# 4KB_SRAM_SCH_EASYEDA.net
KiCad netlist of a schematic drawn in EasyEDA
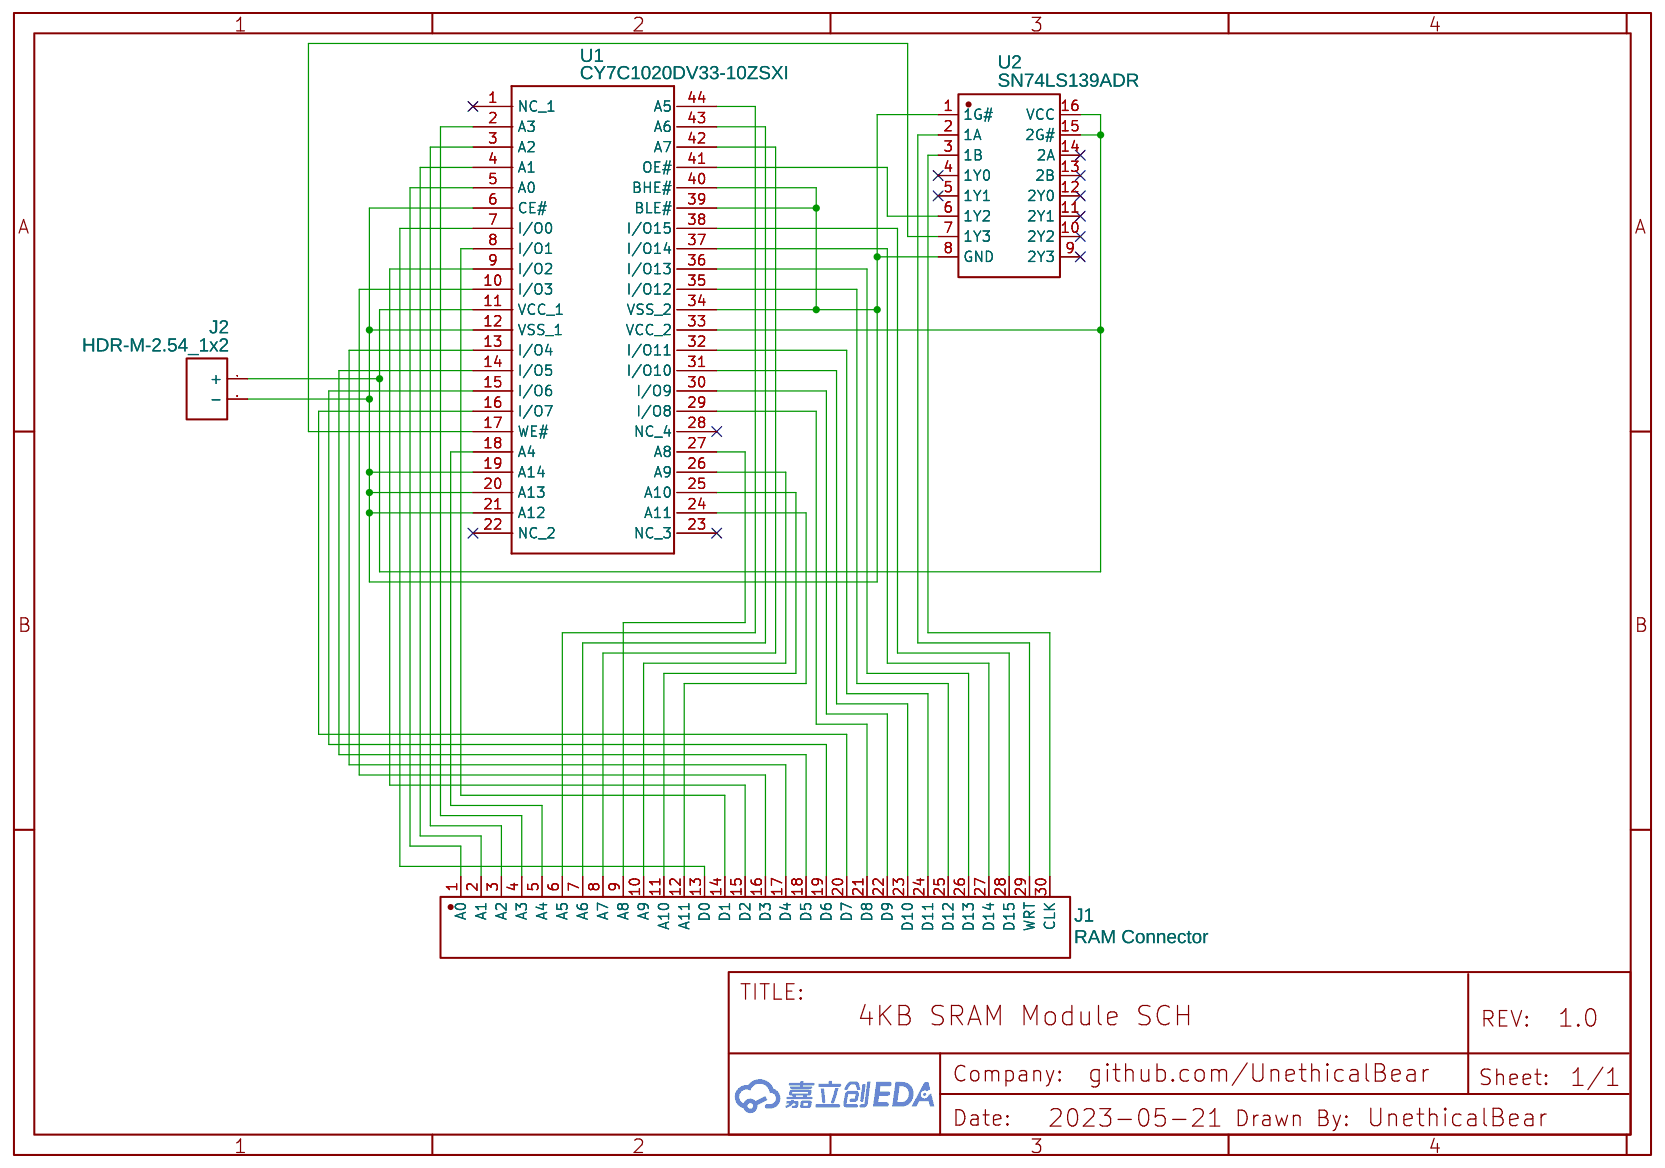
[diagram p0: schematic sheet]

(export (version "E")
  (design (tool "Eeschema 10.0.6"))
  (components
    (comp (ref "J1") (value "RAM Connector") (libsource (lib "") (part "R.C.")))
    (comp (ref "J2")
      (value "HDR-M-2.54_1x2")
      (fields (field (name "BOM_Supplier Part") "C124375"))
      (libsource (lib "") (part "HDR-M-2.54_1x2"))
    )
    (comp (ref "U1") (value "CY7C1020DV33-10ZSXI") (libsource (lib "") (part "CY7C1020DV33-10ZSXI")))
    (comp (ref "U2")
      (value "SN74LS139ADR")
      (fields (field (name "BOM_Supplier Part") "C7738"))
      (libsource (lib "") (part "SN74LS139ADR"))
    )
  )
  (nets
    (net (code "1") (name "Net-(J1-A0)") (class "Default")
      (node (ref "J1") (pin "1") (pinfunction "A0_1") (pintype "unspecified"))
      (node (ref "U1") (pin "5") (pinfunction "A0_5") (pintype "bidirectional"))
    )
    (net (code "2") (name "Net-(J1-A1)") (class "Default")
      (node (ref "J1") (pin "2") (pinfunction "A1_2") (pintype "unspecified"))
      (node (ref "U1") (pin "4") (pinfunction "A1_4") (pintype "bidirectional"))
    )
    (net (code "3") (name "Net-(J1-A2)") (class "Default")
      (node (ref "J1") (pin "3") (pinfunction "A2_3") (pintype "unspecified"))
      (node (ref "U1") (pin "3") (pinfunction "A2_3") (pintype "bidirectional"))
    )
    (net (code "4") (name "Net-(J1-A3)") (class "Default")
      (node (ref "J1") (pin "4") (pinfunction "A3_4") (pintype "unspecified"))
      (node (ref "U1") (pin "2") (pinfunction "A3_2") (pintype "bidirectional"))
    )
    (net (code "5") (name "Net-(J1-A4)") (class "Default")
      (node (ref "J1") (pin "5") (pinfunction "A4_5") (pintype "unspecified"))
      (node (ref "U1") (pin "18") (pinfunction "A4_18") (pintype "bidirectional"))
    )
    (net (code "6") (name "Net-(J1-A5)") (class "Default")
      (node (ref "J1") (pin "6") (pinfunction "A5_6") (pintype "unspecified"))
      (node (ref "U1") (pin "44") (pinfunction "A5_44") (pintype "bidirectional"))
    )
    (net (code "7") (name "Net-(J1-A6)") (class "Default")
      (node (ref "J1") (pin "7") (pinfunction "A6_7") (pintype "unspecified"))
      (node (ref "U1") (pin "43") (pinfunction "A6_43") (pintype "bidirectional"))
    )
    (net (code "8") (name "Net-(J1-A7)") (class "Default")
      (node (ref "J1") (pin "8") (pinfunction "A7_8") (pintype "unspecified"))
      (node (ref "U1") (pin "42") (pinfunction "A7_42") (pintype "bidirectional"))
    )
    (net (code "9") (name "Net-(J1-A8)") (class "Default")
      (node (ref "J1") (pin "9") (pinfunction "A8_9") (pintype "unspecified"))
      (node (ref "U1") (pin "27") (pinfunction "A8_27") (pintype "bidirectional"))
    )
    (net (code "10") (name "Net-(J1-A9)") (class "Default")
      (node (ref "J1") (pin "10") (pinfunction "A9_10") (pintype "unspecified"))
      (node (ref "U1") (pin "26") (pinfunction "A9_26") (pintype "bidirectional"))
    )
    (net (code "11") (name "Net-(J1-A10)") (class "Default")
      (node (ref "J1") (pin "11") (pinfunction "A10_11") (pintype "unspecified"))
      (node (ref "U1") (pin "25") (pinfunction "A10_25") (pintype "bidirectional"))
    )
    (net (code "12") (name "Net-(J1-A11)") (class "Default")
      (node (ref "J1") (pin "12") (pinfunction "A11_12") (pintype "unspecified"))
      (node (ref "U1") (pin "24") (pinfunction "A11_24") (pintype "bidirectional"))
    )
    (net (code "13") (name "Net-(J1-CLK)") (class "Default")
      (node (ref "J1") (pin "30") (pinfunction "CLK_30") (pintype "unspecified"))
      (node (ref "U2") (pin "3") (pinfunction "1B_3") (pintype "unspecified"))
    )
    (net (code "14") (name "Net-(J1-D0)") (class "Default")
      (node (ref "J1") (pin "13") (pinfunction "D0_13") (pintype "unspecified"))
      (node (ref "U1") (pin "7") (pinfunction "I/O0_7") (pintype "bidirectional"))
    )
    (net (code "15") (name "Net-(J1-D1)") (class "Default")
      (node (ref "J1") (pin "14") (pinfunction "D1_14") (pintype "unspecified"))
      (node (ref "U1") (pin "8") (pinfunction "I/O1_8") (pintype "bidirectional"))
    )
    (net (code "16") (name "Net-(J1-D2)") (class "Default")
      (node (ref "J1") (pin "15") (pinfunction "D2_15") (pintype "unspecified"))
      (node (ref "U1") (pin "9") (pinfunction "I/O2_9") (pintype "bidirectional"))
    )
    (net (code "17") (name "Net-(J1-D3)") (class "Default")
      (node (ref "J1") (pin "16") (pinfunction "D3_16") (pintype "unspecified"))
      (node (ref "U1") (pin "10") (pinfunction "I/O3_10") (pintype "bidirectional"))
    )
    (net (code "18") (name "Net-(J1-D4)") (class "Default")
      (node (ref "J1") (pin "17") (pinfunction "D4_17") (pintype "unspecified"))
      (node (ref "U1") (pin "13") (pinfunction "I/O4_13") (pintype "bidirectional"))
    )
    (net (code "19") (name "Net-(J1-D5)") (class "Default")
      (node (ref "J1") (pin "18") (pinfunction "D5_18") (pintype "unspecified"))
      (node (ref "U1") (pin "14") (pinfunction "I/O5_14") (pintype "bidirectional"))
    )
    (net (code "20") (name "Net-(J1-D6)") (class "Default")
      (node (ref "J1") (pin "19") (pinfunction "D6_19") (pintype "unspecified"))
      (node (ref "U1") (pin "15") (pinfunction "I/O6_15") (pintype "bidirectional"))
    )
    (net (code "21") (name "Net-(J1-D7)") (class "Default")
      (node (ref "J1") (pin "20") (pinfunction "D7_20") (pintype "unspecified"))
      (node (ref "U1") (pin "16") (pinfunction "I/O7_16") (pintype "bidirectional"))
    )
    (net (code "22") (name "Net-(J1-D8)") (class "Default")
      (node (ref "J1") (pin "21") (pinfunction "D8_21") (pintype "unspecified"))
      (node (ref "U1") (pin "29") (pinfunction "I/O8_29") (pintype "bidirectional"))
    )
    (net (code "23") (name "Net-(J1-D9)") (class "Default")
      (node (ref "J1") (pin "22") (pinfunction "D9_22") (pintype "unspecified"))
      (node (ref "U1") (pin "30") (pinfunction "I/O9_30") (pintype "bidirectional"))
    )
    (net (code "24") (name "Net-(J1-D10)") (class "Default")
      (node (ref "J1") (pin "23") (pinfunction "D10_23") (pintype "unspecified"))
      (node (ref "U1") (pin "31") (pinfunction "I/O10_31") (pintype "bidirectional"))
    )
    (net (code "25") (name "Net-(J1-D11)") (class "Default")
      (node (ref "J1") (pin "24") (pinfunction "D11_24") (pintype "unspecified"))
      (node (ref "U1") (pin "32") (pinfunction "I/O11_32") (pintype "bidirectional"))
    )
    (net (code "26") (name "Net-(J1-D12)") (class "Default")
      (node (ref "J1") (pin "25") (pinfunction "D12_25") (pintype "unspecified"))
      (node (ref "U1") (pin "35") (pinfunction "I/O12_35") (pintype "bidirectional"))
    )
    (net (code "27") (name "Net-(J1-D13)") (class "Default")
      (node (ref "J1") (pin "26") (pinfunction "D13_26") (pintype "unspecified"))
      (node (ref "U1") (pin "36") (pinfunction "I/O13_36") (pintype "bidirectional"))
    )
    (net (code "28") (name "Net-(J1-D14)") (class "Default")
      (node (ref "J1") (pin "27") (pinfunction "D14_27") (pintype "unspecified"))
      (node (ref "U1") (pin "37") (pinfunction "I/O14_37") (pintype "bidirectional"))
    )
    (net (code "29") (name "Net-(J1-D15)") (class "Default")
      (node (ref "J1") (pin "28") (pinfunction "D15_28") (pintype "unspecified"))
      (node (ref "U1") (pin "38") (pinfunction "I/O15_38") (pintype "bidirectional"))
    )
    (net (code "30") (name "Net-(J1-WRT)") (class "Default")
      (node (ref "J1") (pin "29") (pinfunction "WRT_29") (pintype "unspecified"))
      (node (ref "U2") (pin "2") (pinfunction "1A_2") (pintype "unspecified"))
    )
    (net (code "31") (name "Net-(J2-+)") (class "Default")
      (node (ref "J2") (pin "1") (pinfunction "+_1") (pintype "unspecified"))
      (node (ref "U1") (pin "11") (pinfunction "VCC_1_11") (pintype "bidirectional"))
      (node (ref "U1") (pin "33") (pinfunction "VCC_2_33") (pintype "bidirectional"))
      (node (ref "U2") (pin "15") (pinfunction "2G#_15") (pintype "unspecified"))
      (node (ref "U2") (pin "16") (pinfunction "VCC_16") (pintype "unspecified"))
    )
    (net (code "32") (name "Net-(J2--)") (class "Default")
      (node (ref "J2") (pin "2") (pinfunction "-_2") (pintype "unspecified"))
      (node (ref "U1") (pin "12") (pinfunction "VSS_1_12") (pintype "bidirectional"))
      (node (ref "U1") (pin "19") (pinfunction "A14_19") (pintype "bidirectional"))
      (node (ref "U1") (pin "20") (pinfunction "A13_20") (pintype "bidirectional"))
      (node (ref "U1") (pin "21") (pinfunction "A12_21") (pintype "bidirectional"))
      (node (ref "U1") (pin "34") (pinfunction "VSS_2_34") (pintype "bidirectional"))
      (node (ref "U1") (pin "39") (pinfunction "BLE#_39") (pintype "bidirectional"))
      (node (ref "U1") (pin "40") (pinfunction "BHE#_40") (pintype "bidirectional"))
      (node (ref "U1") (pin "6") (pinfunction "CE#_6") (pintype "bidirectional"))
      (node (ref "U2") (pin "1") (pinfunction "1G#_1") (pintype "unspecified"))
      (node (ref "U2") (pin "8") (pinfunction "GND_8") (pintype "unspecified"))
    )
    (net (code "33") (name "Net-(U1-OE#)") (class "Default")
      (node (ref "U1") (pin "41") (pinfunction "OE#_41") (pintype "bidirectional"))
      (node (ref "U2") (pin "6") (pinfunction "1Y2_6") (pintype "unspecified"))
    )
    (net (code "34") (name "Net-(U1-WE#)") (class "Default")
      (node (ref "U1") (pin "17") (pinfunction "WE#_17") (pintype "bidirectional"))
      (node (ref "U2") (pin "7") (pinfunction "1Y3_7") (pintype "unspecified"))
    )
    (net (code "35") (name "unconnected-(U1-NC_1-Pad1)") (class "Default")
      (node (ref "U1") (pin "1") (pinfunction "NC_1_1") (pintype "bidirectional+no_connect"))
    )
    (net (code "36") (name "unconnected-(U1-NC_2-Pad22)") (class "Default")
      (node (ref "U1") (pin "22") (pinfunction "NC_2_22") (pintype "bidirectional+no_connect"))
    )
    (net (code "37") (name "unconnected-(U1-NC_3-Pad23)") (class "Default")
      (node (ref "U1") (pin "23") (pinfunction "NC_3_23") (pintype "bidirectional+no_connect"))
    )
    (net (code "38") (name "unconnected-(U1-NC_4-Pad28)") (class "Default")
      (node (ref "U1") (pin "28") (pinfunction "NC_4_28") (pintype "bidirectional+no_connect"))
    )
    (net (code "39") (name "unconnected-(U2-1Y0-Pad4)") (class "Default")
      (node (ref "U2") (pin "4") (pinfunction "1Y0_4") (pintype "unspecified+no_connect"))
    )
    (net (code "40") (name "unconnected-(U2-1Y1-Pad5)") (class "Default")
      (node (ref "U2") (pin "5") (pinfunction "1Y1_5") (pintype "unspecified+no_connect"))
    )
    (net (code "41") (name "unconnected-(U2-2A-Pad14)") (class "Default")
      (node (ref "U2") (pin "14") (pinfunction "2A_14") (pintype "unspecified+no_connect"))
    )
    (net (code "42") (name "unconnected-(U2-2B-Pad13)") (class "Default")
      (node (ref "U2") (pin "13") (pinfunction "2B_13") (pintype "unspecified+no_connect"))
    )
    (net (code "43") (name "unconnected-(U2-2Y0-Pad12)") (class "Default")
      (node (ref "U2") (pin "12") (pinfunction "2Y0_12") (pintype "unspecified+no_connect"))
    )
    (net (code "44") (name "unconnected-(U2-2Y1-Pad11)") (class "Default")
      (node (ref "U2") (pin "11") (pinfunction "2Y1_11") (pintype "unspecified+no_connect"))
    )
    (net (code "45") (name "unconnected-(U2-2Y2-Pad10)") (class "Default")
      (node (ref "U2") (pin "10") (pinfunction "2Y2_10") (pintype "unspecified+no_connect"))
    )
    (net (code "46") (name "unconnected-(U2-2Y3-Pad9)") (class "Default")
      (node (ref "U2") (pin "9") (pinfunction "2Y3_9") (pintype "unspecified+no_connect"))
    )
  )
)
